# ButtonsLEDs.net
KiCad netlist of a schematic drawn in EAGLE
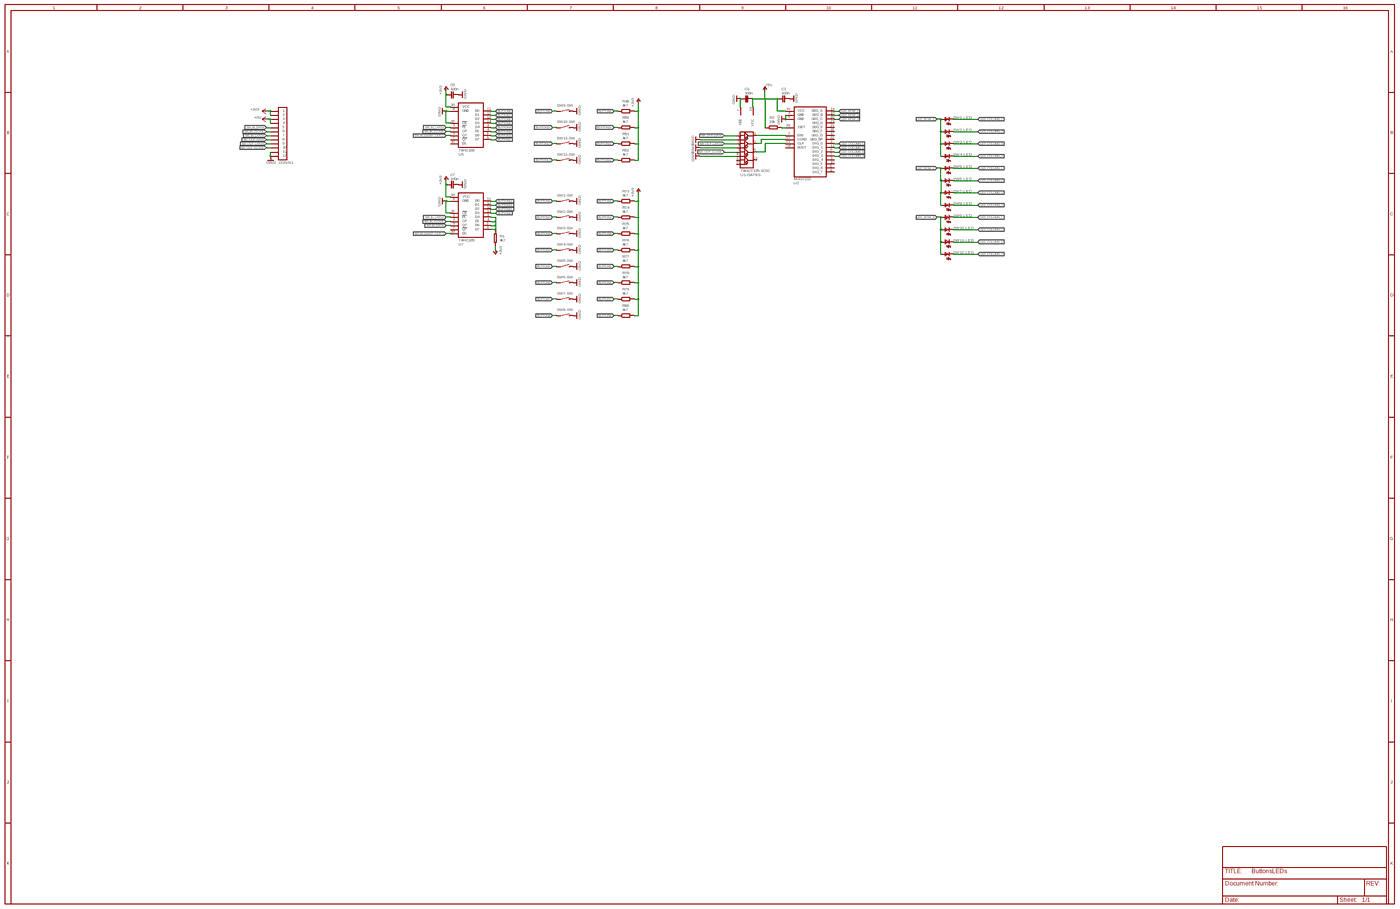
[diagram p0: schematic, sheet 1, overview]
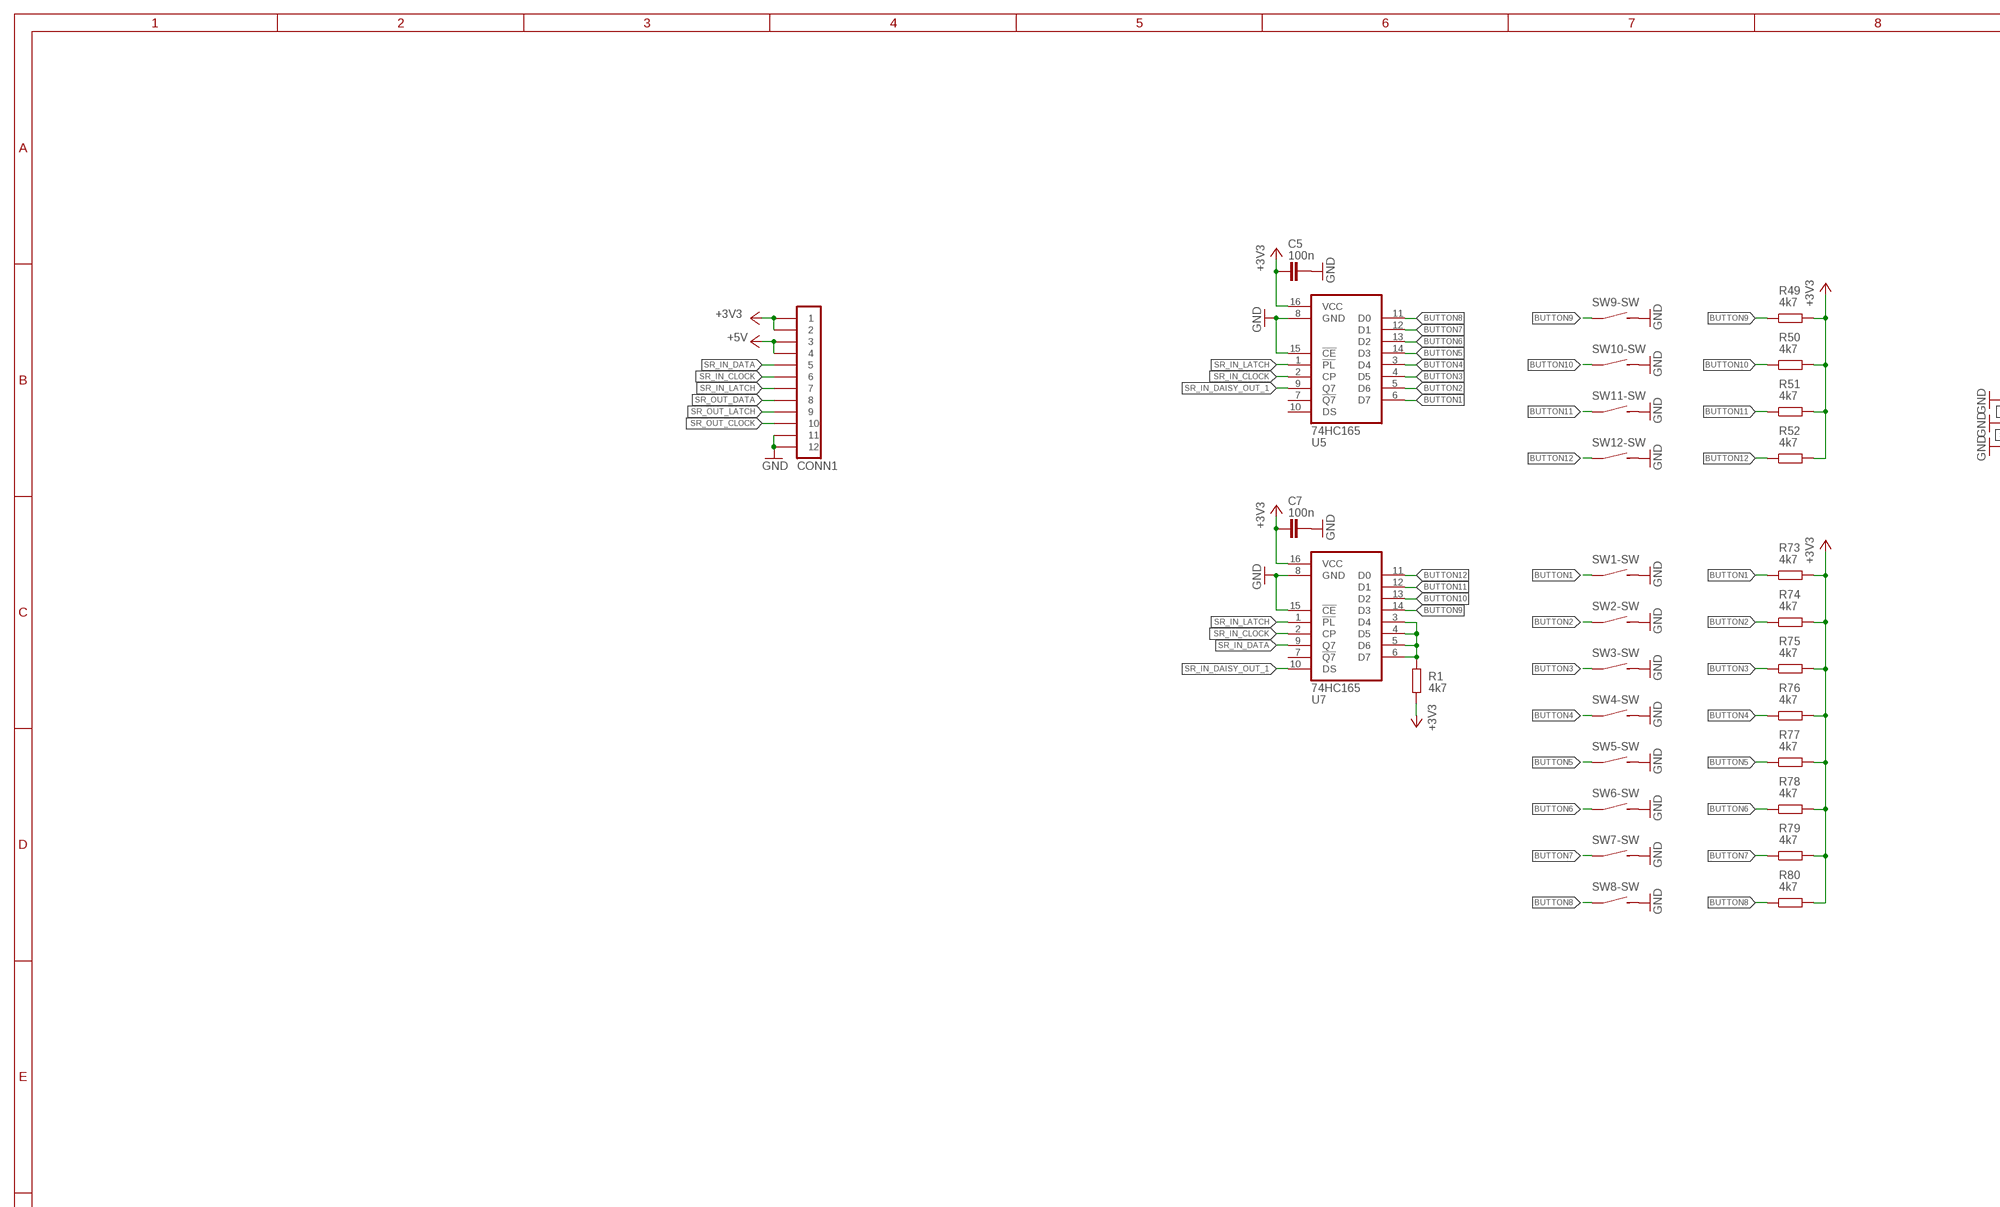
[diagram p1: schematic, sheet 1, part 1 of 4]
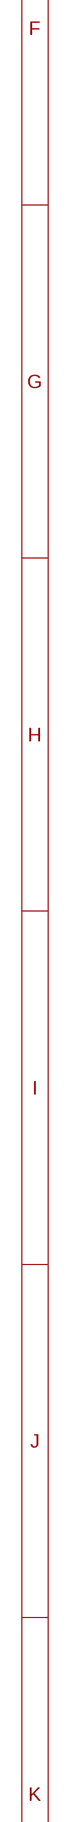
[diagram p2: schematic, sheet 1, part 2 of 4]
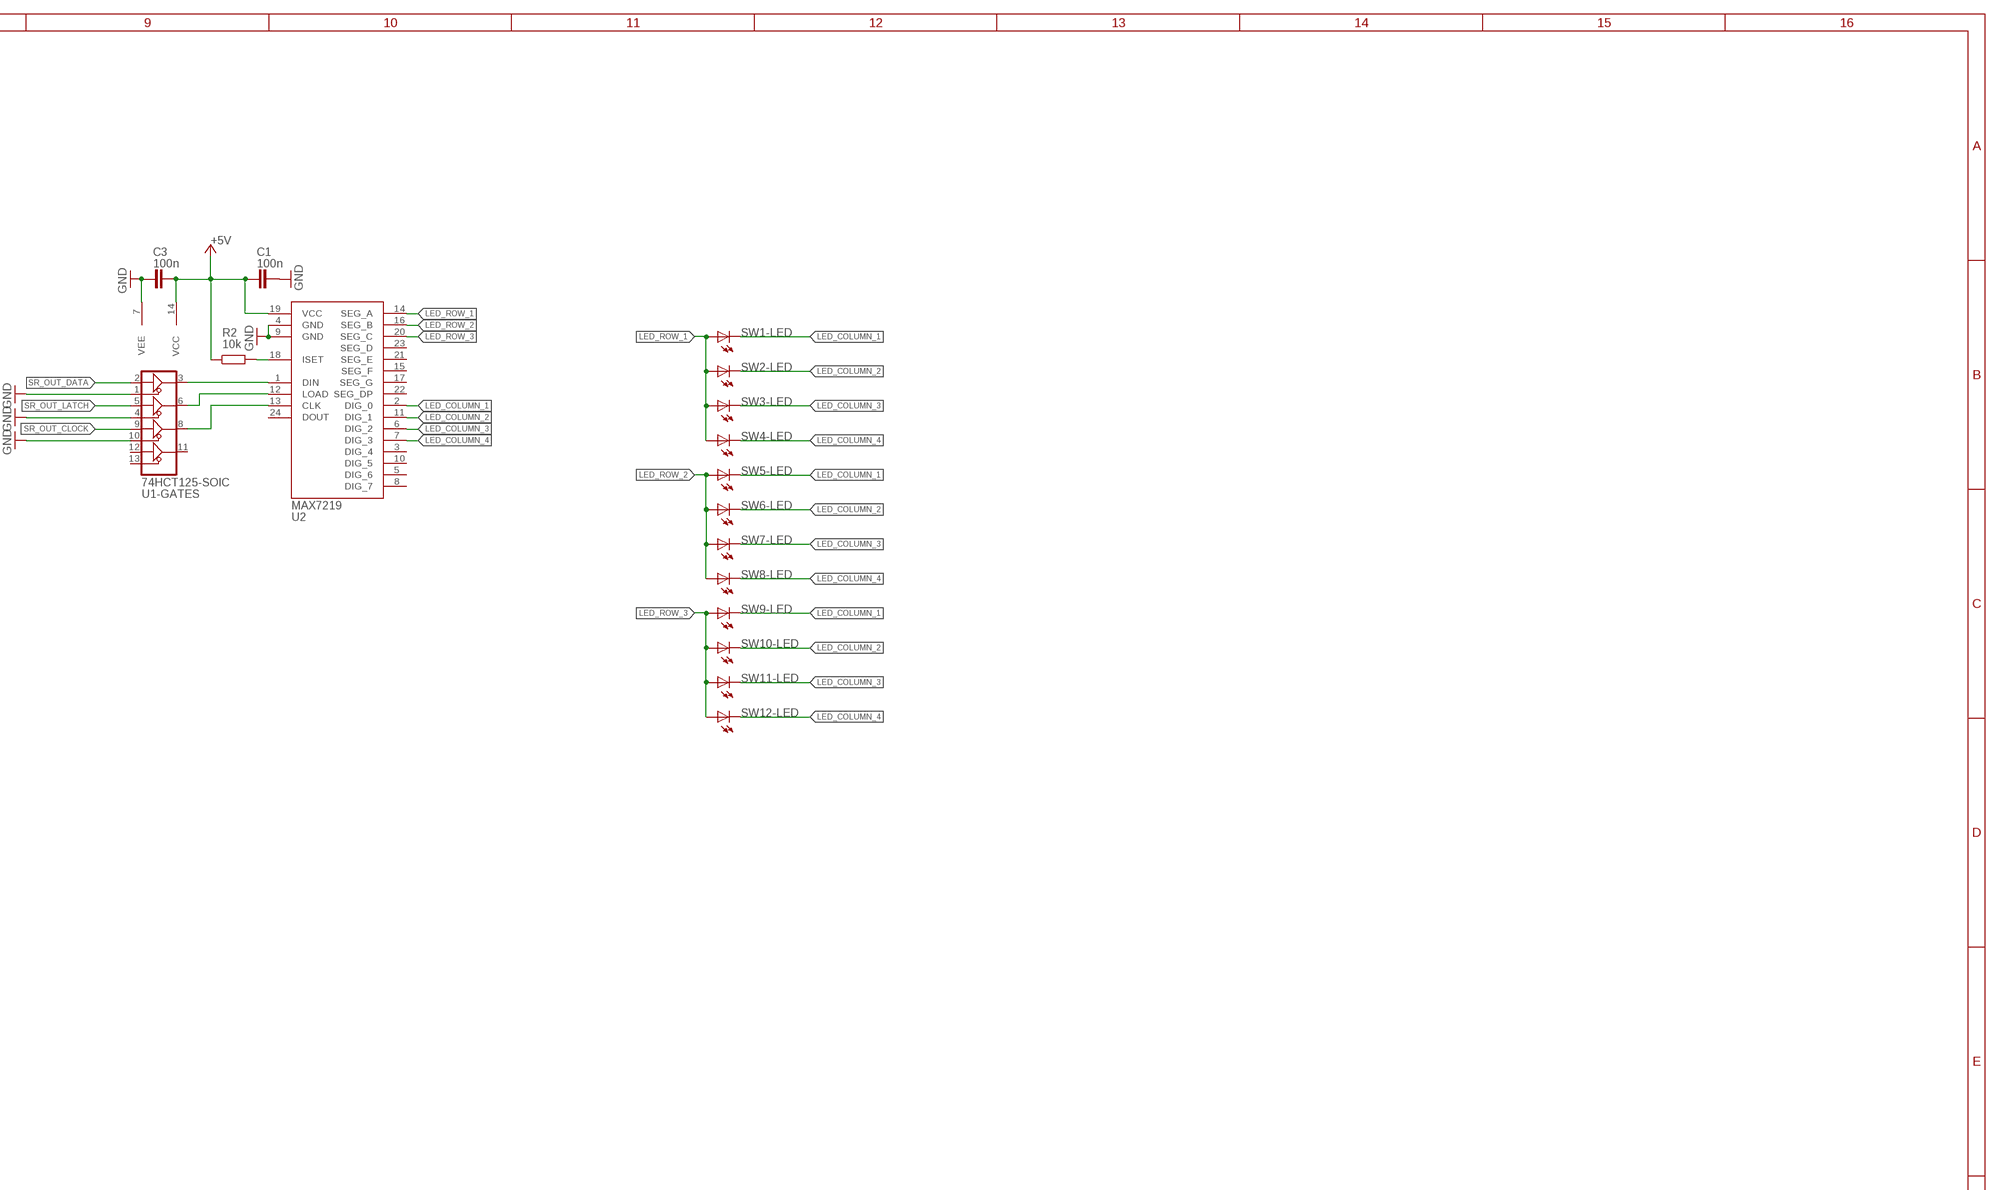
[diagram p3: schematic, sheet 1, part 3 of 4]
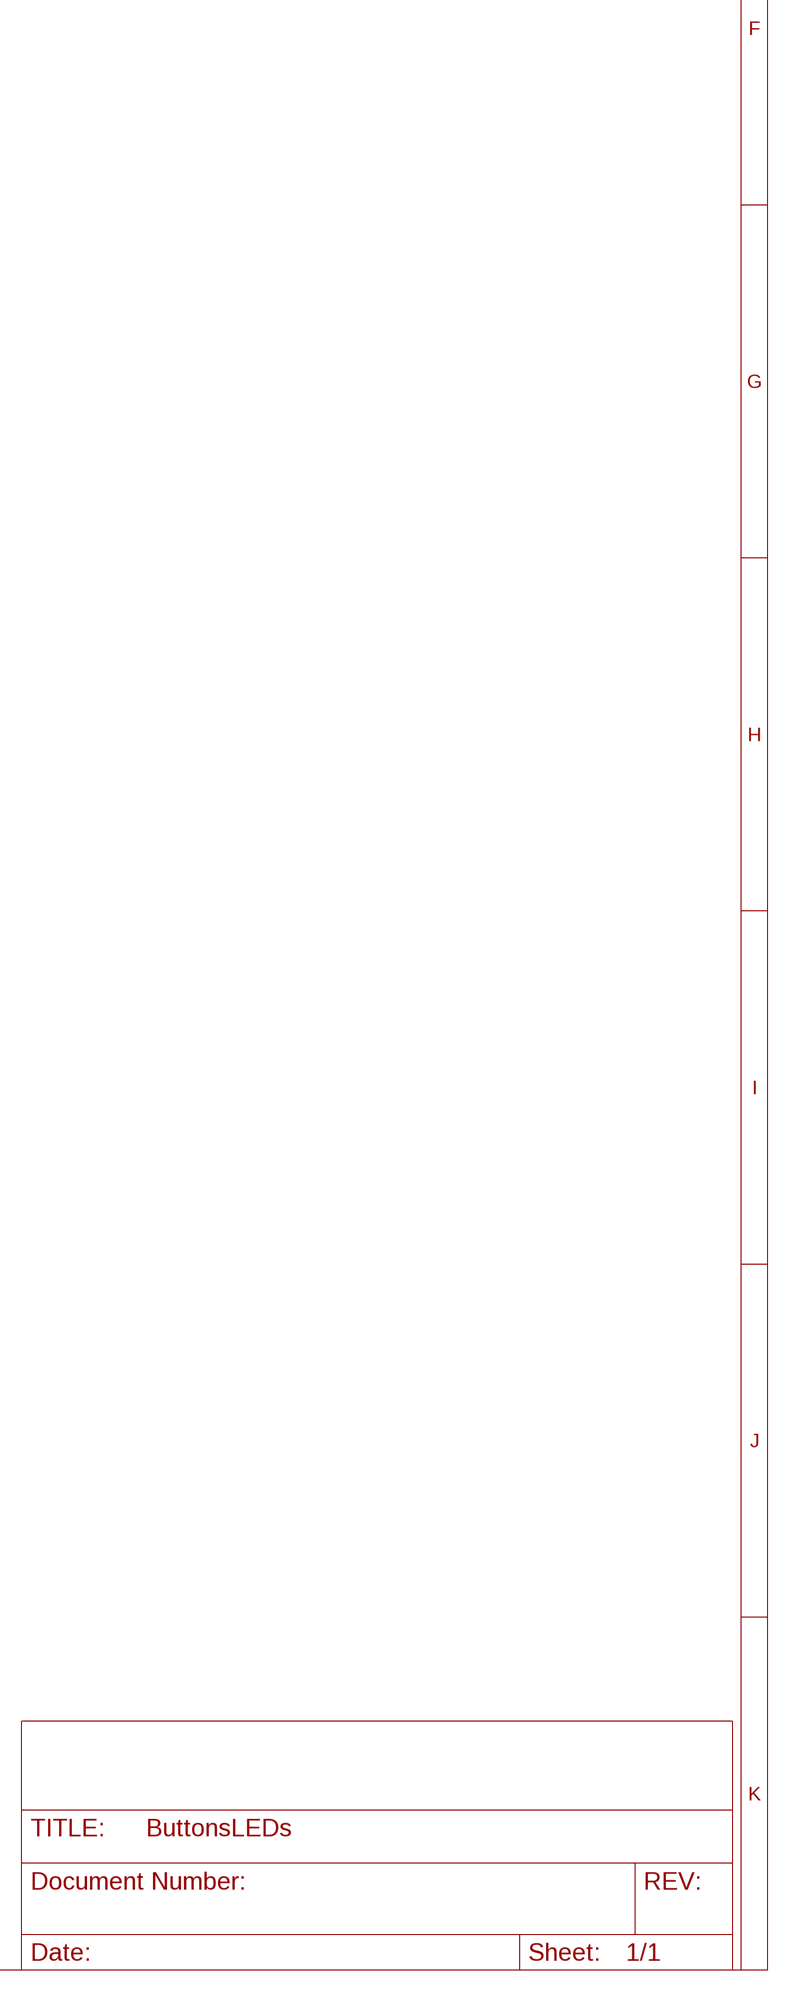
[diagram p4: schematic, sheet 1, part 4 of 4]

(export (version "E")
  (design (tool "Eeschema 10.0.6"))
  (components
    (comp (ref "C1")
      (value "100n")
      (footprint "eagle-import:C0805")
      (libsource (lib "eagle-import") (part "CAPACITOR-0805"))
    )
    (comp (ref "C3")
      (value "100n")
      (footprint "eagle-import:C0805")
      (libsource (lib "eagle-import") (part "CAPACITOR-0805"))
    )
    (comp (ref "C5")
      (value "100n")
      (footprint "eagle-import:C0805")
      (libsource (lib "eagle-import") (part "CAPACITOR-0805"))
    )
    (comp (ref "C7")
      (value "100n")
      (footprint "eagle-import:C0805")
      (libsource (lib "eagle-import") (part "CAPACITOR-0805"))
    )
    (comp (ref "CONN1")
      (value "PINHD-1X12-SMD")
      (footprint "eagle-import:MOLEX-52271-1279")
      (fields (field (name "MANUFACTURER") "Molex") (field (name "MPN") "52271-1279"))
      (libsource (lib "eagle-import") (part "PINHD-1X12-SMD"))
    )
    (comp (ref "R1")
      (value "4k7")
      (footprint "eagle-import:R0805")
      (libsource (lib "eagle-import") (part "RESISTOR-0805"))
    )
    (comp (ref "R2")
      (value "10k")
      (footprint "eagle-import:R0805")
      (libsource (lib "eagle-import") (part "RESISTOR-0805"))
    )
    (comp (ref "R49")
      (value "4k7")
      (footprint "eagle-import:R0805")
      (libsource (lib "eagle-import") (part "RESISTOR-0805"))
    )
    (comp (ref "R50")
      (value "4k7")
      (footprint "eagle-import:R0805")
      (libsource (lib "eagle-import") (part "RESISTOR-0805"))
    )
    (comp (ref "R51")
      (value "4k7")
      (footprint "eagle-import:R0805")
      (libsource (lib "eagle-import") (part "RESISTOR-0805"))
    )
    (comp (ref "R52")
      (value "4k7")
      (footprint "eagle-import:R0805")
      (libsource (lib "eagle-import") (part "RESISTOR-0805"))
    )
    (comp (ref "R73")
      (value "4k7")
      (footprint "eagle-import:R0805")
      (libsource (lib "eagle-import") (part "RESISTOR-0805"))
    )
    (comp (ref "R74")
      (value "4k7")
      (footprint "eagle-import:R0805")
      (libsource (lib "eagle-import") (part "RESISTOR-0805"))
    )
    (comp (ref "R75")
      (value "4k7")
      (footprint "eagle-import:R0805")
      (libsource (lib "eagle-import") (part "RESISTOR-0805"))
    )
    (comp (ref "R76")
      (value "4k7")
      (footprint "eagle-import:R0805")
      (libsource (lib "eagle-import") (part "RESISTOR-0805"))
    )
    (comp (ref "R77")
      (value "4k7")
      (footprint "eagle-import:R0805")
      (libsource (lib "eagle-import") (part "RESISTOR-0805"))
    )
    (comp (ref "R78")
      (value "4k7")
      (footprint "eagle-import:R0805")
      (libsource (lib "eagle-import") (part "RESISTOR-0805"))
    )
    (comp (ref "R79")
      (value "4k7")
      (footprint "eagle-import:R0805")
      (libsource (lib "eagle-import") (part "RESISTOR-0805"))
    )
    (comp (ref "R80")
      (value "4k7")
      (footprint "eagle-import:R0805")
      (libsource (lib "eagle-import") (part "RESISTOR-0805"))
    )
    (comp (ref "SW1")
      (value "OMRON-B3W-9")
      (footprint "eagle-import:OMRON-B3W-9")
      (fields (field (name "MANUFACTURER") "Omron") (field (name "MPN") "B3W-9002"))
      (libsource (lib "eagle-import") (part "OMRON-B3W-9"))
    )
    (comp (ref "SW2")
      (value "OMRON-B3W-9")
      (footprint "eagle-import:OMRON-B3W-9")
      (fields (field (name "MANUFACTURER") "Omron") (field (name "MPN") "B3W-9002"))
      (libsource (lib "eagle-import") (part "OMRON-B3W-9"))
    )
    (comp (ref "SW3")
      (value "OMRON-B3W-9")
      (footprint "eagle-import:OMRON-B3W-9")
      (fields (field (name "MANUFACTURER") "Omron") (field (name "MPN") "B3W-9002"))
      (libsource (lib "eagle-import") (part "OMRON-B3W-9"))
    )
    (comp (ref "SW4")
      (value "OMRON-B3W-9")
      (footprint "eagle-import:OMRON-B3W-9")
      (fields (field (name "MANUFACTURER") "Omron") (field (name "MPN") "B3W-9002"))
      (libsource (lib "eagle-import") (part "OMRON-B3W-9"))
    )
    (comp (ref "SW5")
      (value "OMRON-B3W-9")
      (footprint "eagle-import:OMRON-B3W-9")
      (fields (field (name "MANUFACTURER") "Omron") (field (name "MPN") "B3W-9002"))
      (libsource (lib "eagle-import") (part "OMRON-B3W-9"))
    )
    (comp (ref "SW6")
      (value "OMRON-B3W-9")
      (footprint "eagle-import:OMRON-B3W-9")
      (fields (field (name "MANUFACTURER") "Omron") (field (name "MPN") "B3W-9002"))
      (libsource (lib "eagle-import") (part "OMRON-B3W-9"))
    )
    (comp (ref "SW7")
      (value "OMRON-B3W-9")
      (footprint "eagle-import:OMRON-B3W-9")
      (fields (field (name "MANUFACTURER") "Omron") (field (name "MPN") "B3W-9002"))
      (libsource (lib "eagle-import") (part "OMRON-B3W-9"))
    )
    (comp (ref "SW8")
      (value "OMRON-B3W-9")
      (footprint "eagle-import:OMRON-B3W-9")
      (fields (field (name "MANUFACTURER") "Omron") (field (name "MPN") "B3W-9002"))
      (libsource (lib "eagle-import") (part "OMRON-B3W-9"))
    )
    (comp (ref "SW9")
      (value "OMRON-B3W-9")
      (footprint "eagle-import:OMRON-B3W-9")
      (fields (field (name "MANUFACTURER") "Omron") (field (name "MPN") "B3W-9002"))
      (libsource (lib "eagle-import") (part "OMRON-B3W-9"))
    )
    (comp (ref "SW10")
      (value "OMRON-B3W-9")
      (footprint "eagle-import:OMRON-B3W-9")
      (fields (field (name "MANUFACTURER") "Omron") (field (name "MPN") "B3W-9002"))
      (libsource (lib "eagle-import") (part "OMRON-B3W-9"))
    )
    (comp (ref "SW11")
      (value "OMRON-B3W-9")
      (footprint "eagle-import:OMRON-B3W-9")
      (fields (field (name "MANUFACTURER") "Omron") (field (name "MPN") "B3W-9002"))
      (libsource (lib "eagle-import") (part "OMRON-B3W-9"))
    )
    (comp (ref "SW12")
      (value "OMRON-B3W-9")
      (footprint "eagle-import:OMRON-B3W-9")
      (fields (field (name "MANUFACTURER") "Omron") (field (name "MPN") "B3W-9002"))
      (libsource (lib "eagle-import") (part "OMRON-B3W-9"))
    )
    (comp (ref "U1")
      (value "74HCT125-SOIC")
      (footprint "eagle-import:SOIC14")
      (fields (field (name "MANUFACTURER") "Nexperia") (field (name "MPN") "74HCT125D"))
      (libsource (lib "eagle-import") (part "74125-SOICHCT"))
    )
    (comp (ref "U2")
      (value "MAX7219")
      (footprint "eagle-import:SO24-W")
      (libsource (lib "eagle-import") (part "MAX7219"))
    )
    (comp (ref "U5")
      (value "74HC165")
      (footprint "eagle-import:SO16")
      (fields (field (name "MANUFACTURER") "Nexperia") (field (name "MPN") "74HC165D"))
      (libsource (lib "eagle-import") (part "74165HC"))
    )
    (comp (ref "U7")
      (value "74HC165")
      (footprint "eagle-import:SO16")
      (fields (field (name "MANUFACTURER") "Nexperia") (field (name "MPN") "74HC165D"))
      (libsource (lib "eagle-import") (part "74165HC"))
    )
  )
  (nets
    (net (code "1") (name "+3V3") (class "Default")
      (node (ref "C5") (pin "1") (pinfunction "1_1") (pintype "passive"))
      (node (ref "C7") (pin "1") (pinfunction "1_1") (pintype "passive"))
      (node (ref "CONN1") (pin "1") (pinfunction "1_1") (pintype "passive"))
      (node (ref "CONN1") (pin "2") (pinfunction "2_2") (pintype "passive"))
      (node (ref "R1") (pin "2") (pinfunction "2_2") (pintype "passive"))
      (node (ref "R49") (pin "2") (pinfunction "2_2") (pintype "passive"))
      (node (ref "R50") (pin "2") (pinfunction "2_2") (pintype "passive"))
      (node (ref "R51") (pin "2") (pinfunction "2_2") (pintype "passive"))
      (node (ref "R52") (pin "2") (pinfunction "2_2") (pintype "passive"))
      (node (ref "R73") (pin "2") (pinfunction "2_2") (pintype "passive"))
      (node (ref "R74") (pin "2") (pinfunction "2_2") (pintype "passive"))
      (node (ref "R75") (pin "2") (pinfunction "2_2") (pintype "passive"))
      (node (ref "R76") (pin "2") (pinfunction "2_2") (pintype "passive"))
      (node (ref "R77") (pin "2") (pinfunction "2_2") (pintype "passive"))
      (node (ref "R78") (pin "2") (pinfunction "2_2") (pintype "passive"))
      (node (ref "R79") (pin "2") (pinfunction "2_2") (pintype "passive"))
      (node (ref "R80") (pin "2") (pinfunction "2_2") (pintype "passive"))
      (node (ref "U5") (pin "16") (pinfunction "VCC_16") (pintype "power_in"))
      (node (ref "U7") (pin "16") (pinfunction "VCC_16") (pintype "power_in"))
    )
    (net (code "2") (name "+5V") (class "Default")
      (node (ref "C1") (pin "1") (pinfunction "1_1") (pintype "passive"))
      (node (ref "C3") (pin "1") (pinfunction "1_1") (pintype "passive"))
      (node (ref "CONN1") (pin "3") (pinfunction "3_3") (pintype "passive"))
      (node (ref "CONN1") (pin "4") (pinfunction "4_4") (pintype "passive"))
      (node (ref "R2") (pin "1") (pinfunction "1_1") (pintype "passive"))
      (node (ref "U1") (pin "14") (pinfunction "VCC_14") (pintype "passive"))
      (node (ref "U2") (pin "19") (pinfunction "VCC_19") (pintype "power_in"))
    )
    (net (code "3") (name "BUTTON1") (class "Default")
      (node (ref "R73") (pin "1") (pinfunction "1_1") (pintype "passive"))
      (node (ref "SW1") (pin "1") (pinfunction "1_1") (pintype "passive"))
      (node (ref "U5") (pin "6") (pinfunction "D7_6") (pintype "input"))
    )
    (net (code "4") (name "BUTTON2") (class "Default")
      (node (ref "R74") (pin "1") (pinfunction "1_1") (pintype "passive"))
      (node (ref "SW2") (pin "1") (pinfunction "1_1") (pintype "passive"))
      (node (ref "U5") (pin "5") (pinfunction "D6_5") (pintype "input"))
    )
    (net (code "5") (name "BUTTON3") (class "Default")
      (node (ref "R75") (pin "1") (pinfunction "1_1") (pintype "passive"))
      (node (ref "SW3") (pin "1") (pinfunction "1_1") (pintype "passive"))
      (node (ref "U5") (pin "4") (pinfunction "D5_4") (pintype "input"))
    )
    (net (code "6") (name "BUTTON4") (class "Default")
      (node (ref "R76") (pin "1") (pinfunction "1_1") (pintype "passive"))
      (node (ref "SW4") (pin "1") (pinfunction "1_1") (pintype "passive"))
      (node (ref "U5") (pin "3") (pinfunction "D4_3") (pintype "input"))
    )
    (net (code "7") (name "BUTTON5") (class "Default")
      (node (ref "R77") (pin "1") (pinfunction "1_1") (pintype "passive"))
      (node (ref "SW5") (pin "1") (pinfunction "1_1") (pintype "passive"))
      (node (ref "U5") (pin "14") (pinfunction "D3_14") (pintype "input"))
    )
    (net (code "8") (name "BUTTON6") (class "Default")
      (node (ref "R78") (pin "1") (pinfunction "1_1") (pintype "passive"))
      (node (ref "SW6") (pin "1") (pinfunction "1_1") (pintype "passive"))
      (node (ref "U5") (pin "13") (pinfunction "D2_13") (pintype "input"))
    )
    (net (code "9") (name "BUTTON7") (class "Default")
      (node (ref "R79") (pin "1") (pinfunction "1_1") (pintype "passive"))
      (node (ref "SW7") (pin "1") (pinfunction "1_1") (pintype "passive"))
      (node (ref "U5") (pin "12") (pinfunction "D1_12") (pintype "input"))
    )
    (net (code "10") (name "BUTTON8") (class "Default")
      (node (ref "R80") (pin "1") (pinfunction "1_1") (pintype "passive"))
      (node (ref "SW8") (pin "1") (pinfunction "1_1") (pintype "passive"))
      (node (ref "U5") (pin "11") (pinfunction "D0_11") (pintype "input"))
    )
    (net (code "11") (name "BUTTON9") (class "Default")
      (node (ref "R49") (pin "1") (pinfunction "1_1") (pintype "passive"))
      (node (ref "SW9") (pin "1") (pinfunction "1_1") (pintype "passive"))
      (node (ref "U7") (pin "14") (pinfunction "D3_14") (pintype "input"))
    )
    (net (code "12") (name "BUTTON10") (class "Default")
      (node (ref "R50") (pin "1") (pinfunction "1_1") (pintype "passive"))
      (node (ref "SW10") (pin "1") (pinfunction "1_1") (pintype "passive"))
      (node (ref "U7") (pin "13") (pinfunction "D2_13") (pintype "input"))
    )
    (net (code "13") (name "BUTTON11") (class "Default")
      (node (ref "R51") (pin "1") (pinfunction "1_1") (pintype "passive"))
      (node (ref "SW11") (pin "1") (pinfunction "1_1") (pintype "passive"))
      (node (ref "U7") (pin "12") (pinfunction "D1_12") (pintype "input"))
    )
    (net (code "14") (name "BUTTON12") (class "Default")
      (node (ref "R52") (pin "1") (pinfunction "1_1") (pintype "passive"))
      (node (ref "SW12") (pin "1") (pinfunction "1_1") (pintype "passive"))
      (node (ref "U7") (pin "11") (pinfunction "D0_11") (pintype "input"))
    )
    (net (code "15") (name "GND") (class "Default")
      (node (ref "C1") (pin "2") (pinfunction "2_2") (pintype "passive"))
      (node (ref "C3") (pin "2") (pinfunction "2_2") (pintype "passive"))
      (node (ref "C5") (pin "2") (pinfunction "2_2") (pintype "passive"))
      (node (ref "C7") (pin "2") (pinfunction "2_2") (pintype "passive"))
      (node (ref "CONN1") (pin "11") (pinfunction "11_11") (pintype "passive"))
      (node (ref "CONN1") (pin "12") (pinfunction "12_12") (pintype "passive"))
      (node (ref "SW1") (pin "3") (pinfunction "2_3") (pintype "passive"))
      (node (ref "SW10") (pin "3") (pinfunction "2_3") (pintype "passive"))
      (node (ref "SW11") (pin "3") (pinfunction "2_3") (pintype "passive"))
      (node (ref "SW12") (pin "3") (pinfunction "2_3") (pintype "passive"))
      (node (ref "SW2") (pin "3") (pinfunction "2_3") (pintype "passive"))
      (node (ref "SW3") (pin "3") (pinfunction "2_3") (pintype "passive"))
      (node (ref "SW4") (pin "3") (pinfunction "2_3") (pintype "passive"))
      (node (ref "SW5") (pin "3") (pinfunction "2_3") (pintype "passive"))
      (node (ref "SW6") (pin "3") (pinfunction "2_3") (pintype "passive"))
      (node (ref "SW7") (pin "3") (pinfunction "2_3") (pintype "passive"))
      (node (ref "SW8") (pin "3") (pinfunction "2_3") (pintype "passive"))
      (node (ref "SW9") (pin "3") (pinfunction "2_3") (pintype "passive"))
      (node (ref "U1") (pin "1") (pinfunction "1~{(OE})_1") (pintype "bidirectional"))
      (node (ref "U1") (pin "10") (pinfunction "3~{(OE})_10") (pintype "bidirectional"))
      (node (ref "U1") (pin "4") (pinfunction "2~{(OE})_4") (pintype "bidirectional"))
      (node (ref "U1") (pin "7") (pinfunction "VEE_7") (pintype "passive"))
      (node (ref "U2") (pin "4") (pinfunction "GND_4") (pintype "power_in"))
      (node (ref "U2") (pin "9") (pinfunction "GND_9") (pintype "power_in"))
      (node (ref "U5") (pin "15") (pinfunction "~{CE}_15") (pintype "input"))
      (node (ref "U5") (pin "8") (pinfunction "GND_8") (pintype "power_in"))
      (node (ref "U7") (pin "15") (pinfunction "~{CE}_15") (pintype "input"))
      (node (ref "U7") (pin "8") (pinfunction "GND_8") (pintype "power_in"))
    )
    (net (code "16") (name "LED_COLUMN_1") (class "Default")
      (node (ref "SW1") (pin "6-C") (pinfunction "C_6-C") (pintype "passive"))
      (node (ref "SW5") (pin "6-C") (pinfunction "C_6-C") (pintype "passive"))
      (node (ref "SW9") (pin "6-C") (pinfunction "C_6-C") (pintype "passive"))
      (node (ref "U2") (pin "2") (pinfunction "DIG_0_2") (pintype "output"))
    )
    (net (code "17") (name "LED_COLUMN_2") (class "Default")
      (node (ref "SW10") (pin "6-C") (pinfunction "C_6-C") (pintype "passive"))
      (node (ref "SW2") (pin "6-C") (pinfunction "C_6-C") (pintype "passive"))
      (node (ref "SW6") (pin "6-C") (pinfunction "C_6-C") (pintype "passive"))
      (node (ref "U2") (pin "11") (pinfunction "DIG_1_11") (pintype "output"))
    )
    (net (code "18") (name "LED_COLUMN_3") (class "Default")
      (node (ref "SW11") (pin "6-C") (pinfunction "C_6-C") (pintype "passive"))
      (node (ref "SW3") (pin "6-C") (pinfunction "C_6-C") (pintype "passive"))
      (node (ref "SW7") (pin "6-C") (pinfunction "C_6-C") (pintype "passive"))
      (node (ref "U2") (pin "6") (pinfunction "DIG_2_6") (pintype "output"))
    )
    (net (code "19") (name "LED_COLUMN_4") (class "Default")
      (node (ref "SW12") (pin "6-C") (pinfunction "C_6-C") (pintype "passive"))
      (node (ref "SW4") (pin "6-C") (pinfunction "C_6-C") (pintype "passive"))
      (node (ref "SW8") (pin "6-C") (pinfunction "C_6-C") (pintype "passive"))
      (node (ref "U2") (pin "7") (pinfunction "DIG_3_7") (pintype "output"))
    )
    (net (code "20") (name "LED_ROW_1") (class "Default")
      (node (ref "SW1") (pin "6-A") (pinfunction "A_6-A") (pintype "passive"))
      (node (ref "SW2") (pin "6-A") (pinfunction "A_6-A") (pintype "passive"))
      (node (ref "SW3") (pin "6-A") (pinfunction "A_6-A") (pintype "passive"))
      (node (ref "SW4") (pin "6-A") (pinfunction "A_6-A") (pintype "passive"))
      (node (ref "U2") (pin "14") (pinfunction "SEG_A_14") (pintype "output"))
    )
    (net (code "21") (name "LED_ROW_2") (class "Default")
      (node (ref "SW5") (pin "6-A") (pinfunction "A_6-A") (pintype "passive"))
      (node (ref "SW6") (pin "6-A") (pinfunction "A_6-A") (pintype "passive"))
      (node (ref "SW7") (pin "6-A") (pinfunction "A_6-A") (pintype "passive"))
      (node (ref "SW8") (pin "6-A") (pinfunction "A_6-A") (pintype "passive"))
      (node (ref "U2") (pin "16") (pinfunction "SEG_B_16") (pintype "output"))
    )
    (net (code "22") (name "LED_ROW_3") (class "Default")
      (node (ref "SW10") (pin "6-A") (pinfunction "A_6-A") (pintype "passive"))
      (node (ref "SW11") (pin "6-A") (pinfunction "A_6-A") (pintype "passive"))
      (node (ref "SW12") (pin "6-A") (pinfunction "A_6-A") (pintype "passive"))
      (node (ref "SW9") (pin "6-A") (pinfunction "A_6-A") (pintype "passive"))
      (node (ref "U2") (pin "20") (pinfunction "SEG_C_20") (pintype "output"))
    )
    (net (code "23") (name "Net-(U1A-1Y)") (class "Default")
      (node (ref "U1") (pin "3") (pinfunction "1Y_3") (pintype "bidirectional"))
      (node (ref "U2") (pin "1") (pinfunction "DIN_1") (pintype "input"))
    )
    (net (code "24") (name "Net-(U1A-2Y)") (class "Default")
      (node (ref "U1") (pin "6") (pinfunction "2Y_6") (pintype "bidirectional"))
      (node (ref "U2") (pin "12") (pinfunction "LOAD_12") (pintype "input"))
    )
    (net (code "25") (name "Net-(U1A-3Y)") (class "Default")
      (node (ref "U1") (pin "8") (pinfunction "3Y_8") (pintype "bidirectional"))
      (node (ref "U2") (pin "13") (pinfunction "CLK_13") (pintype "input"))
    )
    (net (code "26") (name "Net-(U2-ISET)") (class "Default")
      (node (ref "R2") (pin "2") (pinfunction "2_2") (pintype "passive"))
      (node (ref "U2") (pin "18") (pinfunction "ISET_18") (pintype "input"))
    )
    (net (code "27") (name "Net-(U7-D4)") (class "Default")
      (node (ref "R1") (pin "1") (pinfunction "1_1") (pintype "passive"))
      (node (ref "U7") (pin "3") (pinfunction "D4_3") (pintype "input"))
      (node (ref "U7") (pin "4") (pinfunction "D5_4") (pintype "input"))
      (node (ref "U7") (pin "5") (pinfunction "D6_5") (pintype "input"))
      (node (ref "U7") (pin "6") (pinfunction "D7_6") (pintype "input"))
    )
    (net (code "28") (name "SR_IN_CLOCK") (class "Default")
      (node (ref "CONN1") (pin "6") (pinfunction "6_6") (pintype "passive"))
      (node (ref "U5") (pin "2") (pinfunction "CP_2") (pintype "bidirectional"))
      (node (ref "U7") (pin "2") (pinfunction "CP_2") (pintype "bidirectional"))
    )
    (net (code "29") (name "SR_IN_DAISY_OUT_1") (class "Default")
      (node (ref "U5") (pin "9") (pinfunction "Q7_9") (pintype "output"))
      (node (ref "U7") (pin "10") (pinfunction "DS_10") (pintype "bidirectional"))
    )
    (net (code "30") (name "SR_IN_DATA") (class "Default")
      (node (ref "CONN1") (pin "5") (pinfunction "5_5") (pintype "passive"))
      (node (ref "U7") (pin "9") (pinfunction "Q7_9") (pintype "output"))
    )
    (net (code "31") (name "SR_IN_LATCH") (class "Default")
      (node (ref "CONN1") (pin "7") (pinfunction "7_7") (pintype "passive"))
      (node (ref "U5") (pin "1") (pinfunction "~{PL}_1") (pintype "input"))
      (node (ref "U7") (pin "1") (pinfunction "~{PL}_1") (pintype "input"))
    )
    (net (code "32") (name "SR_OUT_CLOCK") (class "Default")
      (node (ref "CONN1") (pin "10") (pinfunction "10_10") (pintype "passive"))
      (node (ref "U1") (pin "9") (pinfunction "3A_9") (pintype "bidirectional"))
    )
    (net (code "33") (name "SR_OUT_DATA") (class "Default")
      (node (ref "CONN1") (pin "8") (pinfunction "8_8") (pintype "passive"))
      (node (ref "U1") (pin "2") (pinfunction "1A_2") (pintype "bidirectional"))
    )
    (net (code "34") (name "SR_OUT_LATCH") (class "Default")
      (node (ref "CONN1") (pin "9") (pinfunction "9_9") (pintype "passive"))
      (node (ref "U1") (pin "5") (pinfunction "2A_5") (pintype "bidirectional"))
    )
    (net (code "35") (name "unconnected-(U1A-4A-Pad12)") (class "Default")
      (node (ref "U1") (pin "12") (pinfunction "4A_12") (pintype "bidirectional"))
    )
    (net (code "36") (name "unconnected-(U1A-4Y-Pad11)") (class "Default")
      (node (ref "U1") (pin "11") (pinfunction "4Y_11") (pintype "bidirectional"))
    )
    (net (code "37") (name "unconnected-(U1A-4~{(OE})-Pad13)") (class "Default")
      (node (ref "U1") (pin "13") (pinfunction "4~{(OE})_13") (pintype "bidirectional"))
    )
    (net (code "38") (name "unconnected-(U2-DIG_4-Pad3)") (class "Default")
      (node (ref "U2") (pin "3") (pinfunction "DIG_4_3") (pintype "output"))
    )
    (net (code "39") (name "unconnected-(U2-DIG_5-Pad10)") (class "Default")
      (node (ref "U2") (pin "10") (pinfunction "DIG_5_10") (pintype "output"))
    )
    (net (code "40") (name "unconnected-(U2-DIG_6-Pad5)") (class "Default")
      (node (ref "U2") (pin "5") (pinfunction "DIG_6_5") (pintype "output"))
    )
    (net (code "41") (name "unconnected-(U2-DIG_7-Pad8)") (class "Default")
      (node (ref "U2") (pin "8") (pinfunction "DIG_7_8") (pintype "output"))
    )
    (net (code "42") (name "unconnected-(U2-DOUT-Pad24)") (class "Default")
      (node (ref "U2") (pin "24") (pinfunction "DOUT_24") (pintype "output"))
    )
    (net (code "43") (name "unconnected-(U2-SEG_D-Pad23)") (class "Default")
      (node (ref "U2") (pin "23") (pinfunction "SEG_D_23") (pintype "output"))
    )
    (net (code "44") (name "unconnected-(U2-SEG_DP-Pad22)") (class "Default")
      (node (ref "U2") (pin "22") (pinfunction "SEG_DP_22") (pintype "output"))
    )
    (net (code "45") (name "unconnected-(U2-SEG_E-Pad21)") (class "Default")
      (node (ref "U2") (pin "21") (pinfunction "SEG_E_21") (pintype "output"))
    )
    (net (code "46") (name "unconnected-(U2-SEG_F-Pad15)") (class "Default")
      (node (ref "U2") (pin "15") (pinfunction "SEG_F_15") (pintype "output"))
    )
    (net (code "47") (name "unconnected-(U2-SEG_G-Pad17)") (class "Default")
      (node (ref "U2") (pin "17") (pinfunction "SEG_G_17") (pintype "output"))
    )
    (net (code "48") (name "unconnected-(U5-DS-Pad10)") (class "Default")
      (node (ref "U5") (pin "10") (pinfunction "DS_10") (pintype "bidirectional"))
    )
    (net (code "49") (name "unconnected-(U5-~{Q7}-Pad7)") (class "Default")
      (node (ref "U5") (pin "7") (pinfunction "~{Q7}_7") (pintype "output"))
    )
    (net (code "50") (name "unconnected-(U7-~{Q7}-Pad7)") (class "Default")
      (node (ref "U7") (pin "7") (pinfunction "~{Q7}_7") (pintype "output"))
    )
  )
)
